# MicroDial_Data_Log_V2_Part4.net
KiCad netlist of a schematic drawn in Altium Designer
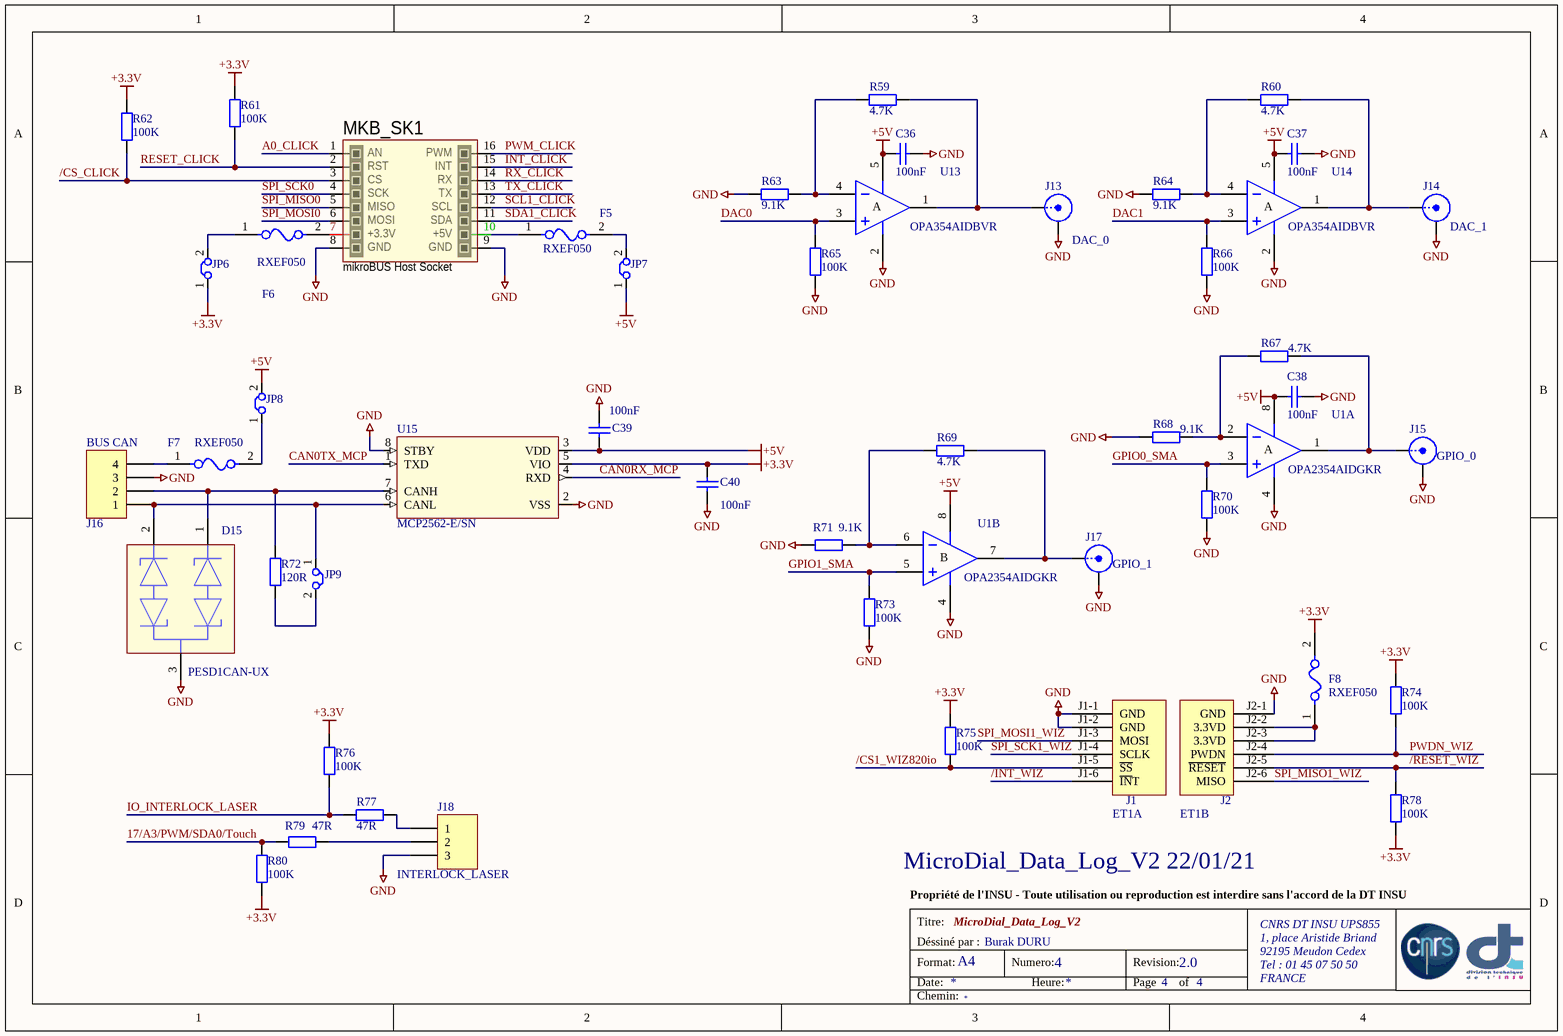
[diagram p0: MicroDial_Data_Log_V2_Part4.SchDoc]

(export (version "E")
  (design (tool "Eeschema 10.0.6"))
  (components
    (comp (ref "C36")
      (value "100nF")
      (footprint "C603")
      (fields (field (name "Comment") "Capacitor CMS"))
      (libsource (lib "pSDLA") (part "Cap"))
    )
    (comp (ref "C37")
      (value "100nF")
      (footprint "C603")
      (fields (field (name "Comment") "Capacitor CMS"))
      (libsource (lib "pSDLA") (part "Cap"))
    )
    (comp (ref "C38")
      (value "100nF")
      (footprint "C603")
      (fields (field (name "Comment") "Capacitor CMS"))
      (libsource (lib "pSDLA") (part "Cap"))
    )
    (comp (ref "C39")
      (value "100nF")
      (footprint "C603")
      (fields (field (name "Comment") "Capacitor CMS"))
      (libsource (lib "pSDLA") (part "Cap"))
    )
    (comp (ref "C40")
      (value "100nF")
      (footprint "C603")
      (fields (field (name "Comment") "Capacitor CMS"))
      (libsource (lib "pSDLA") (part "Cap"))
    )
    (comp (ref "D15")
      (value "PESD1CAN-UX")
      (footprint "SOT323 (SC70) - PESD1CAN-UX")
      (description "Circuit de protection ESD, 50 V, SOT-323, 3 Broche(s), 150 W, PESD1 Series")
      (libsource (lib "MicroDial_burak") (part "PESD1CAN-UX"))
    )
    (comp (ref "ET1")
      (value "Module ETHERNET WIZNET WIZ820IO")
      (footprint "WIZ820io-V1.0")
      (description "IC MODULE W5200+MAG JACK Ethernet Contrôleur 10/100 Base-T/TX PHY SPI Interface Module WIZ820IO")
      (libsource (lib "MicroDial_burak") (part "WIZ820IO"))
    )
    (comp (ref "F5")
      (value "RXEF050")
      (footprint "FP-RXEF050-MFG")
      (libsource (lib "MicroDial") (part "RXEF050"))
    )
    (comp (ref "F6")
      (value "RXEF050")
      (footprint "FP-RXEF050-MFG")
      (libsource (lib "MicroDial") (part "RXEF050"))
    )
    (comp (ref "F7")
      (value "RXEF050")
      (footprint "FP-RXEF050-MFG")
      (libsource (lib "MicroDial") (part "RXEF050"))
    )
    (comp (ref "F8")
      (value "RXEF050")
      (footprint "FP-RXEF050-MFG")
      (libsource (lib "MicroDial") (part "RXEF050"))
    )
    (comp (ref "J13")
      (value "DAC_0")
      (footprint "SMB125B1")
      (description "SMB1252B1-3GT30-50")
      (libsource (lib "pSDLA") (part "SMB1252B1-3GT30-50"))
    )
    (comp (ref "J14")
      (value "DAC_1")
      (footprint "SMB125B1")
      (description "SMB1252B1-3GT30-50")
      (libsource (lib "pSDLA") (part "SMB1252B1-3GT30-50"))
    )
    (comp (ref "J15")
      (value "GPIO_0")
      (footprint "SMA R125.680.000")
      (description "RADIALL - R125680000")
      (libsource (lib "pSDLA") (part "SMA RADIALL - R125680000"))
    )
    (comp (ref "J16")
      (value "BUS CAN")
      (footprint "PHOENIX CONTACT MC 1,5/ 4-G-3,81 - 1803293")
      (description "PHOENIX CONTACT MC 1,5/ 4-G-3,81 - 1803293")
      (libsource (lib "pSDLA") (part "PHOENIX CONTACT MC 1,5/ 4-G-3,81 - 1803293"))
    )
    (comp (ref "J17")
      (value "GPIO_1")
      (footprint "SMA R125.680.000")
      (description "RADIALL - R125680000")
      (libsource (lib "pSDLA") (part "SMA RADIALL - R125680000"))
    )
    (comp (ref "J18")
      (value "INTERLOCK_LASER")
      (footprint "Molex 90136-2203 - UPDATE")
      (description "Molex 90136-2203 CGRID3 Simple Rangée Coudé 3V")
      (libsource (lib "pSDLA") (part "Molex 90136-2203"))
    )
    (comp (ref "JP6")
      (value "Cavalier 1 Positions 1-2")
      (footprint "Molex 90120-0762")
      (description "Jumper 2 Wire")
      (libsource (lib "pSDLA") (part "Jump 12"))
    )
    (comp (ref "JP7")
      (value "Cavalier 1 Positions 1-2")
      (footprint "Molex 90120-0762")
      (description "Jumper 2 Wire")
      (libsource (lib "pSDLA") (part "Jump 12"))
    )
    (comp (ref "JP8")
      (value "Cavalier 1 Positions 1-2")
      (footprint "Molex 90120-0762")
      (description "Jumper 2 Wire")
      (libsource (lib "pSDLA") (part "Jump 12"))
    )
    (comp (ref "JP9")
      (value "Cavalier 1 Positions 1-2")
      (footprint "Molex 90120-0762")
      (description "Jumper 2 Wire")
      (libsource (lib "pSDLA") (part "Jump 12"))
    )
    (comp (ref "MKB_SK1")
      (value "mikroBUS Host Socket")
      (footprint "mikroBUS Host Socket")
      (description "mikroBUS Host Socket (Receptacle carte CLICK)")
      (libsource (lib "pSDLA") (part "mikroBUS Host Socket"))
    )
    (comp (ref "R59")
      (value "4.7K")
      (footprint "MMA204")
      (fields (field (name "Comment") "Res"))
      (libsource (lib "pSDLA") (part "Res"))
    )
    (comp (ref "R60")
      (value "4.7K")
      (footprint "MMA204")
      (fields (field (name "Comment") "Res"))
      (libsource (lib "pSDLA") (part "Res"))
    )
    (comp (ref "R61")
      (value "100K")
      (footprint "R603")
      (description "CRGP0603F100K - Résistance à puce CMS, 100 kohm, ± 1%, 250 mW, 0603 [1608 Metric], Couche épaisse")
      (fields (field (name "Comment") "Res"))
      (libsource (lib "") (part "Res_1"))
    )
    (comp (ref "R62")
      (value "100K")
      (footprint "R603")
      (description "CRGP0603F100K - Résistance à puce CMS, 100 kohm, ± 1%, 250 mW, 0603 [1608 Metric], Couche épaisse")
      (fields (field (name "Comment") "Res"))
      (libsource (lib "") (part "Res_1"))
    )
    (comp (ref "R63")
      (value "9.1K")
      (footprint "MMA204")
      (fields (field (name "Comment") "Res"))
      (libsource (lib "pSDLA") (part "Res"))
    )
    (comp (ref "R64")
      (value "9.1K")
      (footprint "MMA204")
      (fields (field (name "Comment") "Res"))
      (libsource (lib "pSDLA") (part "Res"))
    )
    (comp (ref "R65")
      (value "100K")
      (footprint "R603")
      (description "CRGP0603F100K - Résistance à puce CMS, 100 kohm, ± 1%, 250 mW, 0603 [1608 Metric], Couche épaisse")
      (fields (field (name "Comment") "Res"))
      (libsource (lib "") (part "Res_1"))
    )
    (comp (ref "R66")
      (value "100K")
      (footprint "R603")
      (description "CRGP0603F100K - Résistance à puce CMS, 100 kohm, ± 1%, 250 mW, 0603 [1608 Metric], Couche épaisse")
      (fields (field (name "Comment") "Res"))
      (libsource (lib "") (part "Res_1"))
    )
    (comp (ref "R67")
      (value "4.7K")
      (footprint "MMA204")
      (fields (field (name "Comment") "Res"))
      (libsource (lib "pSDLA") (part "Res"))
    )
    (comp (ref "R68")
      (value "9.1K")
      (footprint "MMA204")
      (fields (field (name "Comment") "Res"))
      (libsource (lib "pSDLA") (part "Res"))
    )
    (comp (ref "R69")
      (value "4.7K")
      (footprint "MMA204")
      (fields (field (name "Comment") "Res"))
      (libsource (lib "pSDLA") (part "Res"))
    )
    (comp (ref "R70")
      (value "100K")
      (footprint "R603")
      (description "CRGP0603F100K - Résistance à puce CMS, 100 kohm, ± 1%, 250 mW, 0603 [1608 Metric], Couche épaisse")
      (fields (field (name "Comment") "Res"))
      (libsource (lib "") (part "Res_1"))
    )
    (comp (ref "R71")
      (value "9.1K")
      (footprint "MMA204")
      (fields (field (name "Comment") "Res"))
      (libsource (lib "pSDLA") (part "Res"))
    )
    (comp (ref "R72")
      (value "120R")
      (footprint "R603")
      (description "CRGP0603F100K - Résistance à puce CMS, 100 kohm, ± 1%, 250 mW, 0603 [1608 Metric], Couche épaisse")
      (fields (field (name "Comment") "Res"))
      (libsource (lib "") (part "Res_1"))
    )
    (comp (ref "R73")
      (value "100K")
      (footprint "R603")
      (description "CRGP0603F100K - Résistance à puce CMS, 100 kohm, ± 1%, 250 mW, 0603 [1608 Metric], Couche épaisse")
      (fields (field (name "Comment") "Res"))
      (libsource (lib "") (part "Res_1"))
    )
    (comp (ref "R74")
      (value "100K")
      (footprint "R603")
      (description "CRGP0603F100K - Résistance à puce CMS, 100 kohm, ± 1%, 250 mW, 0603 [1608 Metric], Couche épaisse")
      (fields (field (name "Comment") "Res"))
      (libsource (lib "pSDLA") (part "Res"))
    )
    (comp (ref "R75")
      (value "100K")
      (footprint "R603")
      (description "CRGP0603F100K - Résistance à puce CMS, 100 kohm, ± 1%, 250 mW, 0603 [1608 Metric], Couche épaisse")
      (fields (field (name "Comment") "Res"))
      (libsource (lib "") (part "Res_1"))
    )
    (comp (ref "R76")
      (value "100K")
      (footprint "R603")
      (description "CRGP0603F100K - Résistance à puce CMS, 100 kohm, ± 1%, 250 mW, 0603 [1608 Metric], Couche épaisse")
      (fields (field (name "Comment") "Res"))
      (libsource (lib "") (part "Res_1"))
    )
    (comp (ref "R77")
      (value "47R")
      (footprint "R603")
      (description "ERJ-UP3J470V - RES, 47R, 5%, 0.25W, 0603, THICK FILM")
      (fields (field (name "Comment") "Res"))
      (libsource (lib "pSDLA") (part "Res"))
    )
    (comp (ref "R78")
      (value "100K")
      (footprint "R603")
      (description "CRGP0603F100K - Résistance à puce CMS, 100 kohm, ± 1%, 250 mW, 0603 [1608 Metric], Couche épaisse")
      (fields (field (name "Comment") "Res"))
      (libsource (lib "") (part "Res_2"))
    )
    (comp (ref "R79")
      (value "47R")
      (footprint "R603")
      (description "ERJ-UP3J470V - RES, 47R, 5%, 0.25W, 0603, THICK FILM")
      (fields (field (name "Comment") "Res"))
      (libsource (lib "pSDLA") (part "Res"))
    )
    (comp (ref "R80")
      (value "100K")
      (footprint "R603")
      (description "CRGP0603F100K - Résistance à puce CMS, 100 kohm, ± 1%, 250 mW, 0603 [1608 Metric], Couche épaisse")
      (fields (field (name "Comment") "Res"))
      (libsource (lib "") (part "Res_1"))
    )
    (comp (ref "U1")
      (value "OPA2354AIDGKR")
      (footprint "VSSOP-8 (DGK(S-PDSO-G8))")
      (libsource (lib "MicroDial") (part "OPA2354AIDGKR"))
    )
    (comp (ref "U13")
      (value "OPA354AIDBVR")
      (footprint "SOT23-5")
      (description "Amplificateur opérationnel, 1 amplificateur, 250 MHz, 150 V/µs, 2.5V à 5.5V, ± 1.25V à ± 2.75V")
      (libsource (lib "MicroDial") (part "OPA354AIDBVR"))
    )
    (comp (ref "U14")
      (value "OPA354AIDBVR")
      (footprint "SOT23-5")
      (description "Amplificateur opérationnel, 1 amplificateur, 250 MHz, 150 V/µs, 2.5V à 5.5V, ± 1.25V à ± 2.75V")
      (libsource (lib "MicroDial") (part "OPA354AIDBVR"))
    )
    (comp (ref "U15")
      (value "MCP2562-E/SN")
      (footprint "SOIC8N (Narrow) - MCP2562-E")
      (description "MCP2562-E/SN Bus CAN, Émetteur-récepteur, CAN, LIN, 1, 1, 4.5 V, 5.5 V, SOIC")
      (libsource (lib "MicroDial_burak") (part "MCP2562-E/SN"))
    )
  )
  (nets
    (net (code "1") (name "+3.3V") (class "Default")
      (node (ref "C40") (pin "1") (pinfunction "1_1") (pintype "passive"))
      (node (ref "F8") (pin "2") (pinfunction "2_2") (pintype "passive"))
      (node (ref "JP6") (pin "1") (pinfunction "1_1") (pintype "passive"))
      (node (ref "R61") (pin "2") (pinfunction "2_2") (pintype "passive"))
      (node (ref "R62") (pin "2") (pinfunction "2_2") (pintype "passive"))
      (node (ref "R74") (pin "2") (pinfunction "2_2") (pintype "passive"))
      (node (ref "R75") (pin "2") (pinfunction "2_2") (pintype "passive"))
      (node (ref "R76") (pin "2") (pinfunction "2_2") (pintype "passive"))
      (node (ref "R78") (pin "2") (pinfunction "2_2") (pintype "passive"))
      (node (ref "R80") (pin "1") (pinfunction "1_1") (pintype "passive"))
      (node (ref "U15") (pin "5") (pinfunction "VIO_5") (pintype "power_in"))
    )
    (net (code "2") (name "+5V") (class "Default")
      (node (ref "C36") (pin "1") (pinfunction "1_1") (pintype "passive"))
      (node (ref "C37") (pin "1") (pinfunction "1_1") (pintype "passive"))
      (node (ref "C38") (pin "1") (pinfunction "1_1") (pintype "passive"))
      (node (ref "C39") (pin "1") (pinfunction "1_1") (pintype "passive"))
      (node (ref "JP7") (pin "1") (pinfunction "1_1") (pintype "passive"))
      (node (ref "JP8") (pin "2") (pinfunction "2_2") (pintype "passive"))
      (node (ref "U1") (pin "8") (pinfunction "V+_8") (pintype "power_in"))
      (node (ref "U13") (pin "5") (pinfunction "V+_5") (pintype "power_in"))
      (node (ref "U14") (pin "5") (pinfunction "V+_5") (pintype "power_in"))
      (node (ref "U15") (pin "3") (pinfunction "VDD_3") (pintype "power_in"))
    )
    (net (code "3") (name "/17{slash}A3{slash}PWM{slash}SDA0{slash}Touch") (class "Default")
      (node (ref "R79") (pin "1") (pinfunction "1_1") (pintype "passive"))
      (node (ref "R80") (pin "2") (pinfunction "2_2") (pintype "passive"))
    )
    (net (code "4") (name "/A0_CLICK") (class "Default")
      (node (ref "MKB_SK1") (pin "1") (pinfunction "AN_1") (pintype "passive"))
    )
    (net (code "5") (name "/CAN0RX_MCP") (class "Default")
      (node (ref "U15") (pin "4") (pinfunction "RXD_4") (pintype "output"))
    )
    (net (code "6") (name "/CAN0TX_MCP") (class "Default")
      (node (ref "U15") (pin "1") (pinfunction "TXD_1") (pintype "input"))
    )
    (net (code "7") (name "/DAC0") (class "Default")
      (node (ref "R65") (pin "2") (pinfunction "2_2") (pintype "passive"))
      (node (ref "U13") (pin "3") (pinfunction "IN+_3") (pintype "passive"))
    )
    (net (code "8") (name "/DAC1") (class "Default")
      (node (ref "R66") (pin "2") (pinfunction "2_2") (pintype "passive"))
      (node (ref "U14") (pin "3") (pinfunction "IN+_3") (pintype "passive"))
    )
    (net (code "9") (name "/GPIO0_SMA") (class "Default")
      (node (ref "R70") (pin "2") (pinfunction "2_2") (pintype "passive"))
      (node (ref "U1") (pin "3") (pinfunction "IN+_3") (pintype "passive"))
    )
    (net (code "10") (name "/GPIO1_SMA") (class "Default")
      (node (ref "R73") (pin "2") (pinfunction "2_2") (pintype "passive"))
      (node (ref "U1") (pin "5") (pinfunction "IN+_5") (pintype "passive"))
    )
    (net (code "11") (name "/INT_CLICK") (class "Default")
      (node (ref "MKB_SK1") (pin "15") (pinfunction "INT_15") (pintype "passive"))
    )
    (net (code "12") (name "/IO_INTERLOCK_LASER") (class "Default")
      (node (ref "R76") (pin "1") (pinfunction "1_1") (pintype "passive"))
      (node (ref "R77") (pin "1") (pinfunction "1_1") (pintype "passive"))
    )
    (net (code "13") (name "/PWDN_WIZ") (class "Default")
      (node (ref "ET1") (pin "J2-4") (pinfunction "PWDN_J2-4") (pintype "passive"))
      (node (ref "R74") (pin "1") (pinfunction "1_1") (pintype "passive"))
    )
    (net (code "14") (name "/PWM_CLICK") (class "Default")
      (node (ref "MKB_SK1") (pin "16") (pinfunction "PWM_16") (pintype "passive"))
    )
    (net (code "15") (name "/RESET_CLICK") (class "Default")
      (node (ref "MKB_SK1") (pin "2") (pinfunction "RST_2") (pintype "passive"))
      (node (ref "R61") (pin "1") (pinfunction "1_1") (pintype "passive"))
    )
    (net (code "16") (name "/RX_CLICK") (class "Default")
      (node (ref "MKB_SK1") (pin "14") (pinfunction "RX_14") (pintype "passive"))
    )
    (net (code "17") (name "/SCL1_CLICK") (class "Default")
      (node (ref "MKB_SK1") (pin "12") (pinfunction "SCL_12") (pintype "passive"))
    )
    (net (code "18") (name "/SDA1_CLICK") (class "Default")
      (node (ref "MKB_SK1") (pin "11") (pinfunction "SDA_11") (pintype "passive"))
    )
    (net (code "19") (name "/SPI_MISO0") (class "Default")
      (node (ref "MKB_SK1") (pin "5") (pinfunction "MISO_5") (pintype "passive"))
    )
    (net (code "20") (name "/SPI_MISO1_WIZ") (class "Default")
      (node (ref "ET1") (pin "J2-6") (pinfunction "MISO_J2-6") (pintype "passive"))
    )
    (net (code "21") (name "/SPI_MOSI0") (class "Default")
      (node (ref "MKB_SK1") (pin "6") (pinfunction "MOSI_6") (pintype "passive"))
    )
    (net (code "22") (name "/SPI_MOSI1_WIZ") (class "Default")
      (node (ref "ET1") (pin "J1-3") (pinfunction "MOSI_J1-3") (pintype "passive"))
    )
    (net (code "23") (name "/SPI_SCK0") (class "Default")
      (node (ref "MKB_SK1") (pin "4") (pinfunction "SCK_4") (pintype "passive"))
    )
    (net (code "24") (name "/SPI_SCK1_WIZ") (class "Default")
      (node (ref "ET1") (pin "J1-4") (pinfunction "SCLK_J1-4") (pintype "passive"))
    )
    (net (code "25") (name "/TX_CLICK") (class "Default")
      (node (ref "MKB_SK1") (pin "13") (pinfunction "TX_13") (pintype "passive"))
    )
    (net (code "26") (name "/{slash}CS1_WIZ820io") (class "Default")
      (node (ref "ET1") (pin "J1-5") (pinfunction "~{SS}_J1-5") (pintype "passive"))
      (node (ref "R75") (pin "1") (pinfunction "1_1") (pintype "passive"))
    )
    (net (code "27") (name "/{slash}CS_CLICK") (class "Default")
      (node (ref "MKB_SK1") (pin "3") (pinfunction "CS_3") (pintype "passive"))
      (node (ref "R62") (pin "1") (pinfunction "1_1") (pintype "passive"))
    )
    (net (code "28") (name "/{slash}INT_WIZ") (class "Default")
      (node (ref "ET1") (pin "J1-6") (pinfunction "~{IN}T_J1-6") (pintype "passive"))
    )
    (net (code "29") (name "/{slash}RESET_WIZ") (class "Default")
      (node (ref "ET1") (pin "J2-5") (pinfunction "~{RESET}_J2-5") (pintype "passive"))
      (node (ref "R78") (pin "1") (pinfunction "1_1") (pintype "passive"))
    )
    (net (code "30") (name "GND") (class "Default")
      (node (ref "C36") (pin "2") (pinfunction "2_2") (pintype "passive"))
      (node (ref "C37") (pin "2") (pinfunction "2_2") (pintype "passive"))
      (node (ref "C38") (pin "2") (pinfunction "2_2") (pintype "passive"))
      (node (ref "C39") (pin "2") (pinfunction "2_2") (pintype "passive"))
      (node (ref "C40") (pin "2") (pinfunction "2_2") (pintype "passive"))
      (node (ref "D15") (pin "3") (pinfunction "common_cathode_3") (pintype "passive"))
      (node (ref "ET1") (pin "J1-1") (pinfunction "GND_J1-1") (pintype "passive"))
      (node (ref "ET1") (pin "J1-2") (pinfunction "GND_J1-2") (pintype "passive"))
      (node (ref "ET1") (pin "J2-1") (pinfunction "GND_J2-1") (pintype "passive"))
      (node (ref "J13") (pin "2") (pinfunction "Y_2") (pintype "passive"))
      (node (ref "J14") (pin "2") (pinfunction "Y_2") (pintype "passive"))
      (node (ref "J15") (pin "2") (pinfunction "Y_2") (pintype "passive"))
      (node (ref "J16") (pin "3") (pinfunction "3_3") (pintype "passive"))
      (node (ref "J17") (pin "2") (pinfunction "Y_2") (pintype "passive"))
      (node (ref "J18") (pin "3") (pinfunction "3_3") (pintype "passive"))
      (node (ref "MKB_SK1") (pin "8") (pinfunction "GND_8") (pintype "passive"))
      (node (ref "MKB_SK1") (pin "9") (pinfunction "GND_9") (pintype "passive"))
      (node (ref "R63") (pin "1") (pinfunction "1_1") (pintype "passive"))
      (node (ref "R64") (pin "1") (pinfunction "1_1") (pintype "passive"))
      (node (ref "R65") (pin "1") (pinfunction "1_1") (pintype "passive"))
      (node (ref "R66") (pin "1") (pinfunction "1_1") (pintype "passive"))
      (node (ref "R68") (pin "1") (pinfunction "1_1") (pintype "passive"))
      (node (ref "R70") (pin "1") (pinfunction "1_1") (pintype "passive"))
      (node (ref "R71") (pin "1") (pinfunction "1_1") (pintype "passive"))
      (node (ref "R73") (pin "1") (pinfunction "1_1") (pintype "passive"))
      (node (ref "U1") (pin "4") (pinfunction "V-_4") (pintype "power_in"))
      (node (ref "U13") (pin "2") (pinfunction "V-_2") (pintype "power_in"))
      (node (ref "U14") (pin "2") (pinfunction "V-_2") (pintype "power_in"))
      (node (ref "U15") (pin "2") (pinfunction "VSS_2") (pintype "power_in"))
      (node (ref "U15") (pin "8") (pinfunction "STBY_8") (pintype "input"))
    )
    (net (code "31") (name "Net-(D15-cathode_1)") (class "Default")
      (node (ref "D15") (pin "1") (pinfunction "cathode_1_1") (pintype "passive"))
      (node (ref "J16") (pin "2") (pinfunction "2_2") (pintype "passive"))
      (node (ref "R72") (pin "2") (pinfunction "2_2") (pintype "passive"))
      (node (ref "U15") (pin "7") (pinfunction "CANH_7") (pintype "input"))
    )
    (net (code "32") (name "Net-(D15-cathode_2)") (class "Default")
      (node (ref "D15") (pin "2") (pinfunction "cathode_2_2") (pintype "passive"))
      (node (ref "J16") (pin "1") (pinfunction "1_1") (pintype "passive"))
      (node (ref "JP9") (pin "1") (pinfunction "1_1") (pintype "passive"))
      (node (ref "U15") (pin "6") (pinfunction "CANL_6") (pintype "input"))
    )
    (net (code "33") (name "Net-(ET1B-3.3VD-PadJ2-2)") (class "Default")
      (node (ref "ET1") (pin "J2-2") (pinfunction "3.3VD_J2-2") (pintype "passive"))
      (node (ref "ET1") (pin "J2-3") (pinfunction "3.3VD_J2-3") (pintype "passive"))
      (node (ref "F8") (pin "1") (pinfunction "1_1") (pintype "passive"))
    )
    (net (code "34") (name "Net-(F5-Pad2)") (class "Default")
      (node (ref "F5") (pin "2") (pinfunction "2_2") (pintype "passive"))
      (node (ref "JP7") (pin "2") (pinfunction "2_2") (pintype "passive"))
    )
    (net (code "35") (name "Net-(F6-Pad1)") (class "Default")
      (node (ref "F6") (pin "1") (pinfunction "1_1") (pintype "passive"))
      (node (ref "JP6") (pin "2") (pinfunction "2_2") (pintype "passive"))
    )
    (net (code "36") (name "Net-(F7-Pad1)") (class "Default")
      (node (ref "F7") (pin "1") (pinfunction "1_1") (pintype "passive"))
      (node (ref "J16") (pin "4") (pinfunction "4_4") (pintype "passive"))
    )
    (net (code "37") (name "Net-(F7-Pad2)") (class "Default")
      (node (ref "F7") (pin "2") (pinfunction "2_2") (pintype "passive"))
      (node (ref "JP8") (pin "1") (pinfunction "1_1") (pintype "passive"))
    )
    (net (code "38") (name "Net-(J13-X)") (class "Default")
      (node (ref "J13") (pin "1") (pinfunction "X_1") (pintype "passive"))
      (node (ref "R59") (pin "2") (pinfunction "2_2") (pintype "passive"))
      (node (ref "U13") (pin "1") (pinfunction "OUT_1") (pintype "passive"))
    )
    (net (code "39") (name "Net-(J14-X)") (class "Default")
      (node (ref "J14") (pin "1") (pinfunction "X_1") (pintype "passive"))
      (node (ref "R60") (pin "2") (pinfunction "2_2") (pintype "passive"))
      (node (ref "U14") (pin "1") (pinfunction "OUT_1") (pintype "passive"))
    )
    (net (code "40") (name "Net-(J15-X)") (class "Default")
      (node (ref "J15") (pin "1") (pinfunction "X_1") (pintype "passive"))
      (node (ref "R67") (pin "2") (pinfunction "2_2") (pintype "passive"))
      (node (ref "U1") (pin "1") (pinfunction "OUT_1") (pintype "passive"))
    )
    (net (code "41") (name "Net-(J17-X)") (class "Default")
      (node (ref "J17") (pin "1") (pinfunction "X_1") (pintype "passive"))
      (node (ref "R69") (pin "2") (pinfunction "2_2") (pintype "passive"))
      (node (ref "U1") (pin "7") (pinfunction "OUT_7") (pintype "passive"))
    )
    (net (code "42") (name "Net-(J18-Pad1)") (class "Default")
      (node (ref "J18") (pin "1") (pinfunction "1_1") (pintype "passive"))
      (node (ref "R77") (pin "2") (pinfunction "2_2") (pintype "passive"))
    )
    (net (code "43") (name "Net-(J18-Pad2)") (class "Default")
      (node (ref "J18") (pin "2") (pinfunction "2_2") (pintype "passive"))
      (node (ref "R79") (pin "2") (pinfunction "2_2") (pintype "passive"))
    )
    (net (code "44") (name "Net-(JP9-Pad2)") (class "Default")
      (node (ref "JP9") (pin "2") (pinfunction "2_2") (pintype "passive"))
      (node (ref "R72") (pin "1") (pinfunction "1_1") (pintype "passive"))
    )
    (net (code "45") (name "Net-(MKB_SK1-+3.3V)") (class "Default")
      (node (ref "F6") (pin "2") (pinfunction "2_2") (pintype "passive"))
      (node (ref "MKB_SK1") (pin "7") (pinfunction "+3.3V_7") (pintype "passive"))
    )
    (net (code "46") (name "Net-(MKB_SK1-+5V)") (class "Default")
      (node (ref "F5") (pin "1") (pinfunction "1_1") (pintype "passive"))
      (node (ref "MKB_SK1") (pin "10") (pinfunction "+5V_10") (pintype "passive"))
    )
    (net (code "47") (name "Net-(U1A-IN-)") (class "Default")
      (node (ref "R67") (pin "1") (pinfunction "1_1") (pintype "passive"))
      (node (ref "R68") (pin "2") (pinfunction "2_2") (pintype "passive"))
      (node (ref "U1") (pin "2") (pinfunction "IN-_2") (pintype "passive"))
    )
    (net (code "48") (name "Net-(U1B-IN-)") (class "Default")
      (node (ref "R69") (pin "1") (pinfunction "1_1") (pintype "passive"))
      (node (ref "R71") (pin "2") (pinfunction "2_2") (pintype "passive"))
      (node (ref "U1") (pin "6") (pinfunction "IN-_6") (pintype "passive"))
    )
    (net (code "49") (name "Net-(U13-IN-)") (class "Default")
      (node (ref "R59") (pin "1") (pinfunction "1_1") (pintype "passive"))
      (node (ref "R63") (pin "2") (pinfunction "2_2") (pintype "passive"))
      (node (ref "U13") (pin "4") (pinfunction "IN-_4") (pintype "passive"))
    )
    (net (code "50") (name "Net-(U14-IN-)") (class "Default")
      (node (ref "R60") (pin "1") (pinfunction "1_1") (pintype "passive"))
      (node (ref "R64") (pin "2") (pinfunction "2_2") (pintype "passive"))
      (node (ref "U14") (pin "4") (pinfunction "IN-_4") (pintype "passive"))
    )
    (net (code "51") (name "unconnected-(J13-REF-Pad3)") (class "Default")
      (node (ref "J13") (pin "3") (pinfunction "REF_3") (pintype "passive"))
    )
    (net (code "52") (name "unconnected-(J13-REF-Pad4)") (class "Default")
      (node (ref "J13") (pin "4") (pinfunction "REF_4") (pintype "passive"))
    )
    (net (code "53") (name "unconnected-(J13-REF-Pad5)") (class "Default")
      (node (ref "J13") (pin "5") (pinfunction "REF_5") (pintype "passive"))
    )
    (net (code "54") (name "unconnected-(J14-REF-Pad3)") (class "Default")
      (node (ref "J14") (pin "3") (pinfunction "REF_3") (pintype "passive"))
    )
    (net (code "55") (name "unconnected-(J14-REF-Pad4)") (class "Default")
      (node (ref "J14") (pin "4") (pinfunction "REF_4") (pintype "passive"))
    )
    (net (code "56") (name "unconnected-(J14-REF-Pad5)") (class "Default")
      (node (ref "J14") (pin "5") (pinfunction "REF_5") (pintype "passive"))
    )
    (net (code "57") (name "unconnected-(J15-REF-Pad3)") (class "Default")
      (node (ref "J15") (pin "3") (pinfunction "REF_3") (pintype "passive"))
    )
    (net (code "58") (name "unconnected-(J15-REF-Pad4)") (class "Default")
      (node (ref "J15") (pin "4") (pinfunction "REF_4") (pintype "passive"))
    )
    (net (code "59") (name "unconnected-(J15-REF-Pad5)") (class "Default")
      (node (ref "J15") (pin "5") (pinfunction "REF_5") (pintype "passive"))
    )
    (net (code "60") (name "unconnected-(J17-REF-Pad3)") (class "Default")
      (node (ref "J17") (pin "3") (pinfunction "REF_3") (pintype "passive"))
    )
    (net (code "61") (name "unconnected-(J17-REF-Pad4)") (class "Default")
      (node (ref "J17") (pin "4") (pinfunction "REF_4") (pintype "passive"))
    )
    (net (code "62") (name "unconnected-(J17-REF-Pad5)") (class "Default")
      (node (ref "J17") (pin "5") (pinfunction "REF_5") (pintype "passive"))
    )
  )
)
